# ID_logic.net
KiCad netlist of a schematic drawn in Altium Designer
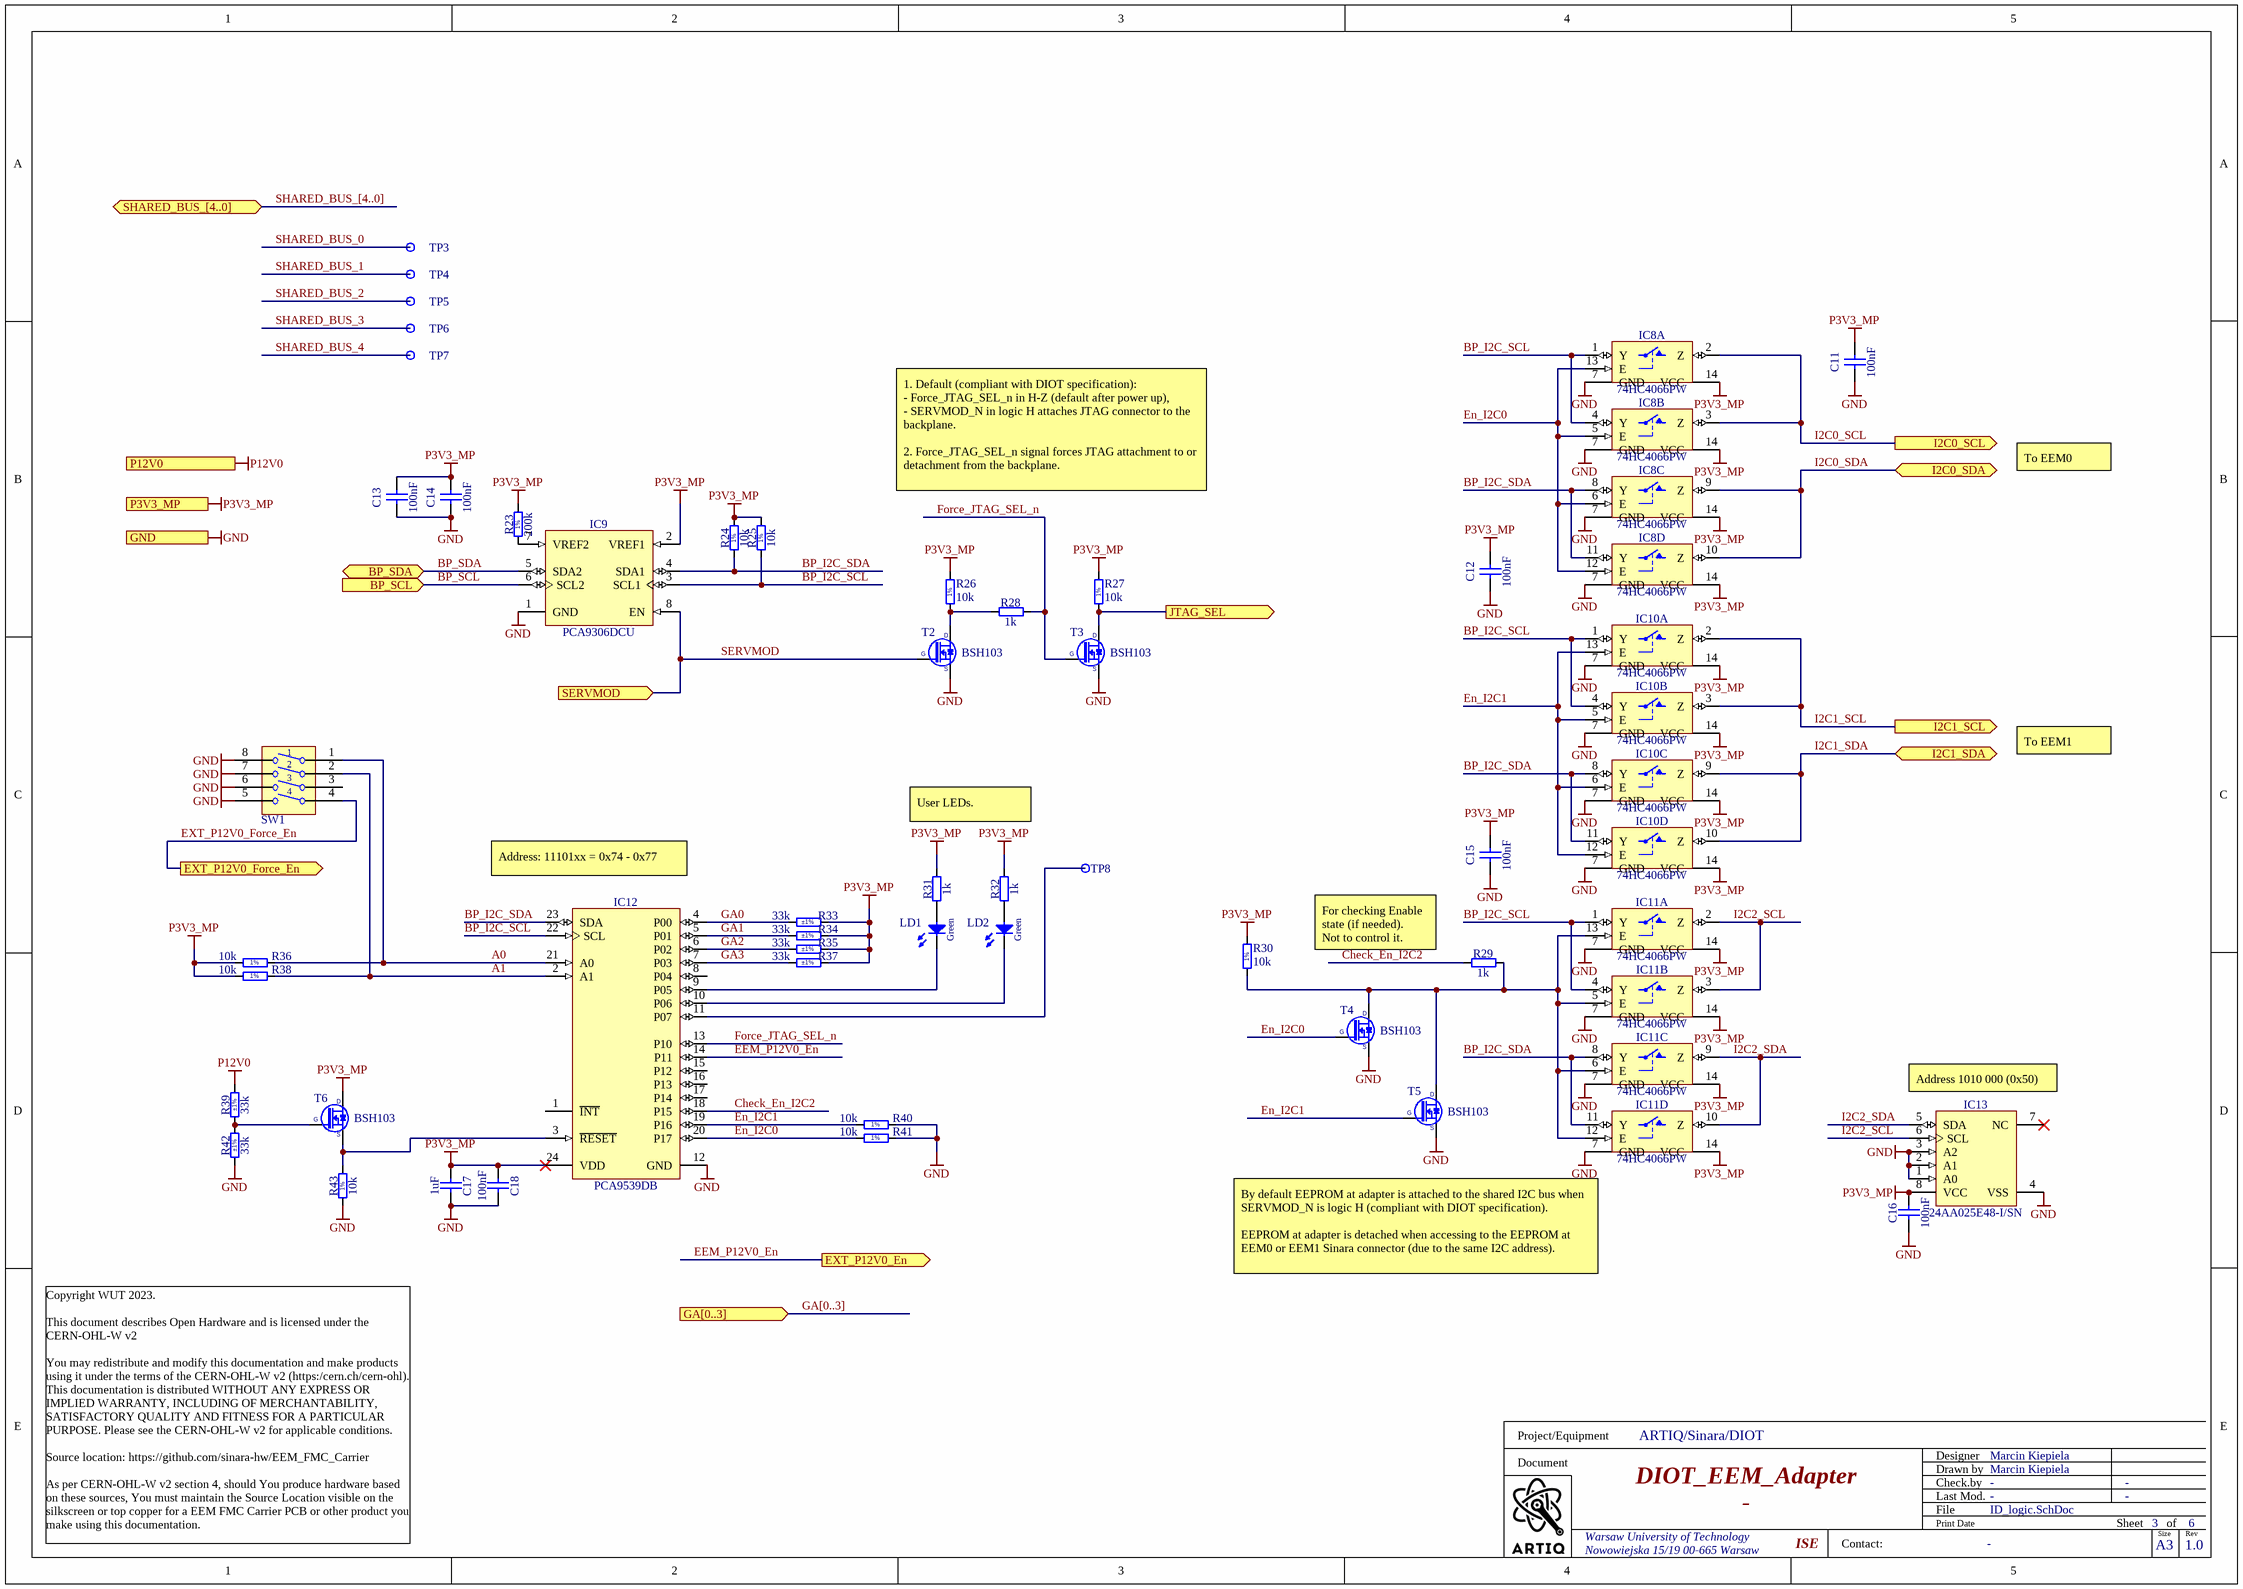
[diagram p0: ID_logic.SchDoc]

(export (version "E")
  (design (tool "Eeschema 10.0.6"))
  (components
    (comp (ref "C11")
      (value "100nF")
      (footprint "CAPC1005X55N")
      (description "Non-polarised capacitor")
      (fields
        (field (name "PART NUMBER") "CC0402_100NF_16V_10%_X7R")
        (field (name "VOLTAGE") "16V")
        (field (name "AUTHOR") "CERN DEM JLC")
      )
      (libsource (lib "Capacitors") (part "Capacitor - non polarized"))
    )
    (comp (ref "C12")
      (value "100nF")
      (footprint "CAPC1005X55N")
      (description "Non-polarised capacitor")
      (fields
        (field (name "PART NUMBER") "CC0402_100NF_16V_10%_X7R")
        (field (name "VOLTAGE") "16V")
        (field (name "AUTHOR") "CERN DEM JLC")
      )
      (libsource (lib "Capacitors") (part "Capacitor - non polarized"))
    )
    (comp (ref "C13")
      (value "100nF")
      (footprint "CAPC1005X55N")
      (description "Non-polarised capacitor")
      (fields
        (field (name "PART NUMBER") "CC0402_100NF_16V_10%_X7R")
        (field (name "VOLTAGE") "16V")
        (field (name "AUTHOR") "CERN DEM JLC")
      )
      (libsource (lib "Capacitors") (part "Capacitor - non polarized"))
    )
    (comp (ref "C14")
      (value "100nF")
      (footprint "CAPC1005X55N")
      (description "Non-polarised capacitor")
      (fields
        (field (name "PART NUMBER") "CC0402_100NF_16V_10%_X7R")
        (field (name "VOLTAGE") "16V")
        (field (name "AUTHOR") "CERN DEM JLC")
      )
      (libsource (lib "Capacitors") (part "Capacitor - non polarized"))
    )
    (comp (ref "C15")
      (value "100nF")
      (footprint "CAPC1005X55N")
      (description "Non-polarised capacitor")
      (fields
        (field (name "PART NUMBER") "CC0402_100NF_16V_10%_X7R")
        (field (name "VOLTAGE") "16V")
        (field (name "AUTHOR") "CERN DEM JLC")
      )
      (libsource (lib "Capacitors") (part "Capacitor - non polarized"))
    )
    (comp (ref "C16")
      (value "100nF")
      (footprint "CAPC1005X55N")
      (description "Non-polarised capacitor")
      (fields
        (field (name "PART NUMBER") "CC0402_100NF_16V_10%_X7R")
        (field (name "VOLTAGE") "16V")
        (field (name "AUTHOR") "CERN DEM JLC")
      )
      (libsource (lib "Capacitors") (part "Capacitor - non polarized"))
    )
    (comp (ref "C17")
      (value "1uF")
      (footprint "CAPC1608X87N")
      (description "Non-polarised capacitor")
      (fields
        (field (name "PART NUMBER") "CC0603_1UF_25V_10%_X7R")
        (field (name "VOLTAGE") "25V")
        (field (name "AUTHOR") "CERN DEM JLC")
      )
      (libsource (lib "Capacitors") (part "Capacitor - non polarized"))
    )
    (comp (ref "C18")
      (value "100nF")
      (footprint "CAPC1005X55N")
      (description "Non-polarised capacitor")
      (fields
        (field (name "PART NUMBER") "CC0402_100NF_16V_10%_X7R")
        (field (name "VOLTAGE") "16V")
        (field (name "AUTHOR") "CERN DEM JLC")
      )
      (libsource (lib "Capacitors") (part "Capacitor - non polarized"))
    )
    (comp (ref "IC8")
      (value "74HC4066PW")
      (footprint "SOP65P640X110-14N")
      (fields (field (name "MANUFACTURER") "NXP SEMICONDUCTORS") (field (name "AUTHOR") "CERN DEM JLC"))
      (libsource (lib "ICs And Semiconductors") (part "4066"))
    )
    (comp (ref "IC9")
      (value "PCA9306DCU")
      (footprint "SOP50P310X90-8N")
      (description "Dual Bidirectional I2C Bus And SMBus Voltage-Level Translator")
      (fields
        (field (name "PART NUMBER") "PCA9306DCUR")
        (field (name "MANUFACTURER") "TEXAS INSTRUMENTS")
        (field (name "AUTHOR") "CERN DEM JLC")
      )
      (libsource (lib "ICs And Semiconductors") (part "PCA9306D"))
    )
    (comp (ref "IC10")
      (value "74HC4066PW")
      (footprint "SOP65P640X110-14N")
      (fields (field (name "MANUFACTURER") "NXP SEMICONDUCTORS") (field (name "AUTHOR") "CERN DEM JLC"))
      (libsource (lib "ICs And Semiconductors") (part "4066"))
    )
    (comp (ref "IC11")
      (value "74HC4066PW")
      (footprint "SOP65P640X110-14N")
      (fields (field (name "MANUFACTURER") "NXP SEMICONDUCTORS") (field (name "AUTHOR") "CERN DEM JLC"))
      (libsource (lib "ICs And Semiconductors") (part "4066"))
    )
    (comp (ref "IC12")
      (value "PCA9539DB")
      (footprint "SOP65P780X200-24N")
      (fields (field (name "MANUFACTURER") "TEXAS INSTRUMENTS") (field (name "AUTHOR") "CERN DEM HF"))
      (libsource (lib "ICs And Semiconductors") (part "PCA9539DB"))
    )
    (comp (ref "IC13")
      (value "24AA025E48-I/SN")
      (footprint "SOIC127P600X175-8N")
      (description "1.7V-5.5V, 2K I2C™ Serial EEPROMs with EUI-48™ Node Identity")
      (fields (field (name "MANUFACTURER") "MICROCHIP TECHNOLOGY") (field (name "AUTHOR") "CERN DEM MR"))
      (libsource (lib "ICs And Semiconductors") (part "24AA025E48-I/SN"))
    )
    (comp (ref "LD1")
      (value "Green")
      (footprint "LED_KINGBRIGHT_KPH-1608CGCK")
      (description "LED Green 1C 2A")
      (fields
        (field (name "MANUFACTURER PART NUMBER") "KPH-1608CGCK")
        (field (name "PART NUMBER") "LED_KINGBRIGHT_KPH-1608CGCK")
        (field (name "AUTHOR") "CERN DEM JLC")
      )
      (libsource (lib "ICs And Semiconductors") (part "LED Green 1C 2A"))
    )
    (comp (ref "LD2")
      (value "Green")
      (footprint "LED_KINGBRIGHT_KPH-1608CGCK")
      (description "LED Green 1C 2A")
      (fields
        (field (name "MANUFACTURER PART NUMBER") "KPH-1608CGCK")
        (field (name "PART NUMBER") "LED_KINGBRIGHT_KPH-1608CGCK")
        (field (name "AUTHOR") "CERN DEM JLC")
      )
      (libsource (lib "ICs And Semiconductors") (part "LED Green 1C 2A"))
    )
    (comp (ref "R23")
      (value "200k")
      (footprint "RESC1005X40N")
      (description "Resistor - 1%")
      (fields
        (field (name "PART NUMBER") "R0402_200K_1%_0.0625W_100PPM")
        (field (name "POWER") "0.0625W")
        (field (name "AUTHOR") "CERN DEM JLC")
      )
      (libsource (lib "Resistors") (part "Resistor - 1%"))
    )
    (comp (ref "R24")
      (value "10k")
      (footprint "RESC1005X40N")
      (description "Resistor - 1%")
      (fields
        (field (name "PART NUMBER") "R0402_10K_1%_0.0625W_100PPM")
        (field (name "POWER") "0.0625W")
        (field (name "AUTHOR") "CERN DEM JLC")
      )
      (libsource (lib "Resistors") (part "Resistor - 1%"))
    )
    (comp (ref "R25")
      (value "10k")
      (footprint "RESC1005X40N")
      (description "Resistor - 1%")
      (fields
        (field (name "PART NUMBER") "R0402_10K_1%_0.0625W_100PPM")
        (field (name "POWER") "0.0625W")
        (field (name "AUTHOR") "CERN DEM JLC")
      )
      (libsource (lib "Resistors") (part "Resistor - 1%"))
    )
    (comp (ref "R26")
      (value "10k")
      (footprint "RESC1005X40N")
      (description "Resistor - 1%")
      (fields
        (field (name "PART NUMBER") "R0402_10K_1%_0.0625W_100PPM")
        (field (name "POWER") "0.0625W")
        (field (name "AUTHOR") "CERN DEM JLC")
      )
      (libsource (lib "Resistors") (part "Resistor - 1%"))
    )
    (comp (ref "R27")
      (value "10k")
      (footprint "RESC1005X40N")
      (description "Resistor - 1%")
      (fields
        (field (name "PART NUMBER") "R0402_10K_1%_0.0625W_100PPM")
        (field (name "POWER") "0.0625W")
        (field (name "AUTHOR") "CERN DEM JLC")
      )
      (libsource (lib "Resistors") (part "Resistor - 1%"))
    )
    (comp (ref "R28")
      (value "1k")
      (footprint "RESC1005X40N")
      (description "Resistor - 1%")
      (fields
        (field (name "PART NUMBER") "R0402_1K_1%_0.0625W_100PPM")
        (field (name "POWER") "0.0625W")
        (field (name "AUTHOR") "CERN DEM JLC")
      )
      (libsource (lib "Resistors") (part "Resistor - 1%"))
    )
    (comp (ref "R29")
      (value "1k")
      (footprint "RESC1005X40N")
      (description "Resistor - 1%")
      (fields
        (field (name "PART NUMBER") "R0402_1K_1%_0.0625W_100PPM")
        (field (name "POWER") "0.0625W")
        (field (name "AUTHOR") "CERN DEM JLC")
      )
      (libsource (lib "Resistors") (part "Resistor - 1%"))
    )
    (comp (ref "R30")
      (value "10k")
      (footprint "RESC1005X40N")
      (description "Resistor - 1%")
      (fields
        (field (name "PART NUMBER") "R0402_10K_1%_0.0625W_100PPM")
        (field (name "POWER") "0.0625W")
        (field (name "AUTHOR") "CERN DEM JLC")
      )
      (libsource (lib "Resistors") (part "Resistor - 1%"))
    )
    (comp (ref "R31")
      (value "1k")
      (footprint "RESC1005X40N")
      (description "Resistor - 1%")
      (fields
        (field (name "PART NUMBER") "R0402_1K_1%_0.0625W_100PPM")
        (field (name "POWER") "0.0625W")
        (field (name "AUTHOR") "CERN DEM JLC")
      )
      (libsource (lib "Resistors") (part "Resistor - 1%"))
    )
    (comp (ref "R32")
      (value "1k")
      (footprint "RESC1005X40N")
      (description "Resistor - 1%")
      (fields
        (field (name "PART NUMBER") "R0402_1K_1%_0.0625W_100PPM")
        (field (name "POWER") "0.0625W")
        (field (name "AUTHOR") "CERN DEM JLC")
      )
      (libsource (lib "Resistors") (part "Resistor - 1%"))
    )
    (comp (ref "R33")
      (value "33k")
      (footprint "RESC1005X40N")
      (description "Resistor - 1%")
      (fields
        (field (name "TOLERANCE") "±1%")
        (field (name "PART NUMBER") "R0402_33K_1%_0.0625W_100PPM")
        (field (name "POWER") "0.0625W")
        (field (name "AUTHOR") "CERN DEM JLC")
      )
      (libsource (lib "Resistors") (part "Resistor - 1%"))
    )
    (comp (ref "R34")
      (value "33k")
      (footprint "RESC1005X40N")
      (description "Resistor - 1%")
      (fields
        (field (name "TOLERANCE") "±1%")
        (field (name "PART NUMBER") "R0402_33K_1%_0.0625W_100PPM")
        (field (name "POWER") "0.0625W")
        (field (name "AUTHOR") "CERN DEM JLC")
      )
      (libsource (lib "Resistors") (part "Resistor - 1%"))
    )
    (comp (ref "R35")
      (value "33k")
      (footprint "RESC1005X40N")
      (description "Resistor - 1%")
      (fields
        (field (name "TOLERANCE") "±1%")
        (field (name "PART NUMBER") "R0402_33K_1%_0.0625W_100PPM")
        (field (name "POWER") "0.0625W")
        (field (name "AUTHOR") "CERN DEM JLC")
      )
      (libsource (lib "Resistors") (part "Resistor - 1%"))
    )
    (comp (ref "R36")
      (value "10k")
      (footprint "RESC1005X40N")
      (description "Resistor - 1%")
      (fields
        (field (name "PART NUMBER") "R0402_10K_1%_0.0625W_100PPM")
        (field (name "POWER") "0.0625W")
        (field (name "AUTHOR") "CERN DEM JLC")
      )
      (libsource (lib "Resistors") (part "Resistor - 1%"))
    )
    (comp (ref "R37")
      (value "33k")
      (footprint "RESC1005X40N")
      (description "Resistor - 1%")
      (fields
        (field (name "TOLERANCE") "±1%")
        (field (name "PART NUMBER") "R0402_33K_1%_0.0625W_100PPM")
        (field (name "POWER") "0.0625W")
        (field (name "AUTHOR") "CERN DEM JLC")
      )
      (libsource (lib "Resistors") (part "Resistor - 1%"))
    )
    (comp (ref "R38")
      (value "10k")
      (footprint "RESC1005X40N")
      (description "Resistor - 1%")
      (fields
        (field (name "PART NUMBER") "R0402_10K_1%_0.0625W_100PPM")
        (field (name "POWER") "0.0625W")
        (field (name "AUTHOR") "CERN DEM JLC")
      )
      (libsource (lib "Resistors") (part "Resistor - 1%"))
    )
    (comp (ref "R39")
      (value "33k")
      (footprint "RESC1005X40N")
      (description "Resistor - 1%")
      (fields
        (field (name "TOLERANCE") "±1%")
        (field (name "PART NUMBER") "R0402_33K_1%_0.0625W_100PPM")
        (field (name "POWER") "0.0625W")
        (field (name "AUTHOR") "CERN DEM JLC")
      )
      (libsource (lib "Resistors") (part "Resistor - 1%"))
    )
    (comp (ref "R40")
      (value "10k")
      (footprint "RESC1005X40N")
      (description "Resistor - 1%")
      (fields
        (field (name "PART NUMBER") "R0402_10K_1%_0.0625W_100PPM")
        (field (name "POWER") "0.0625W")
        (field (name "AUTHOR") "CERN DEM JLC")
      )
      (libsource (lib "Resistors") (part "Resistor - 1%"))
    )
    (comp (ref "R41")
      (value "10k")
      (footprint "RESC1005X40N")
      (description "Resistor - 1%")
      (fields
        (field (name "PART NUMBER") "R0402_10K_1%_0.0625W_100PPM")
        (field (name "POWER") "0.0625W")
        (field (name "AUTHOR") "CERN DEM JLC")
      )
      (libsource (lib "Resistors") (part "Resistor - 1%"))
    )
    (comp (ref "R42")
      (value "33k")
      (footprint "RESC1005X40N")
      (description "Resistor - 1%")
      (fields
        (field (name "TOLERANCE") "±1%")
        (field (name "PART NUMBER") "R0402_33K_1%_0.0625W_100PPM")
        (field (name "POWER") "0.0625W")
        (field (name "AUTHOR") "CERN DEM JLC")
      )
      (libsource (lib "Resistors") (part "Resistor - 1%"))
    )
    (comp (ref "R43")
      (value "10k")
      (footprint "RESC1005X40N")
      (description "Resistor - 1%")
      (fields
        (field (name "PART NUMBER") "R0402_10K_1%_0.0625W_100PPM")
        (field (name "POWER") "0.0625W")
        (field (name "AUTHOR") "CERN DEM JLC")
      )
      (libsource (lib "Resistors") (part "Resistor - 1%"))
    )
    (comp (ref "SW1")
      (value "Switch")
      (footprint "SW_OMRON_A6S-4102-H")
      (description "4 Ways SPST DIP Switch")
      (fields
        (field (name "PART NUMBER") "SW_OMRON_A6S-4102-H")
        (field (name "MANUFACTURER") "OMRON")
        (field (name "AUTHOR") "CERN DEM JMW")
      )
      (libsource (lib "Eletro-mechanical") (part "SW 4x SPST DIP Switch"))
    )
    (comp (ref "T2")
      (value "BSH103")
      (footprint "SOT95P230X110-3N")
      (description "N-CHANNEL MOSFET WITH DIODE")
      (fields (field (name "MANUFACTURER") "NEXPERIA") (field (name "AUTHOR") "CERN DEM JLC"))
      (libsource (lib "ICs And Semiconductors") (part "N-MOSFET-D 1G 2S 3D"))
    )
    (comp (ref "T3")
      (value "BSH103")
      (footprint "SOT95P230X110-3N")
      (description "N-CHANNEL MOSFET WITH DIODE")
      (fields (field (name "MANUFACTURER") "NEXPERIA") (field (name "AUTHOR") "CERN DEM JLC"))
      (libsource (lib "ICs And Semiconductors") (part "N-MOSFET-D 1G 2S 3D"))
    )
    (comp (ref "T4")
      (value "BSH103")
      (footprint "SOT95P230X110-3N")
      (description "N-CHANNEL MOSFET WITH DIODE")
      (fields (field (name "MANUFACTURER") "NEXPERIA") (field (name "AUTHOR") "CERN DEM JLC"))
      (libsource (lib "ICs And Semiconductors") (part "N-MOSFET-D 1G 2S 3D"))
    )
    (comp (ref "T5")
      (value "BSH103")
      (footprint "SOT95P230X110-3N")
      (description "N-CHANNEL MOSFET WITH DIODE")
      (fields (field (name "MANUFACTURER") "NEXPERIA") (field (name "AUTHOR") "CERN DEM JLC"))
      (libsource (lib "ICs And Semiconductors") (part "N-MOSFET-D 1G 2S 3D"))
    )
    (comp (ref "T6")
      (value "BSH103")
      (footprint "SOT95P230X110-3N")
      (description "N-CHANNEL MOSFET WITH DIODE")
      (fields (field (name "MANUFACTURER") "NEXPERIA") (field (name "AUTHOR") "CERN DEM JLC"))
      (libsource (lib "ICs And Semiconductors") (part "N-MOSFET-D 1G 2S 3D"))
    )
    (comp (ref "TP3")
      (value "Test Point")
      (footprint "TPS127")
      (fields (field (name "PART NUMBER") "SMD_PAD_1.27X1.27MM") (field (name "AUTHOR") "CERN DEM JLC"))
      (libsource (lib "Eletro-mechanical") (part "Test Point"))
    )
    (comp (ref "TP4")
      (value "Test Point")
      (footprint "TPS127")
      (fields (field (name "PART NUMBER") "SMD_PAD_1.27X1.27MM") (field (name "AUTHOR") "CERN DEM JLC"))
      (libsource (lib "Eletro-mechanical") (part "Test Point"))
    )
    (comp (ref "TP5")
      (value "Test Point")
      (footprint "TPS127")
      (fields (field (name "PART NUMBER") "SMD_PAD_1.27X1.27MM") (field (name "AUTHOR") "CERN DEM JLC"))
      (libsource (lib "Eletro-mechanical") (part "Test Point"))
    )
    (comp (ref "TP6")
      (value "Test Point")
      (footprint "TPS127")
      (fields (field (name "PART NUMBER") "SMD_PAD_1.27X1.27MM") (field (name "AUTHOR") "CERN DEM JLC"))
      (libsource (lib "Eletro-mechanical") (part "Test Point"))
    )
    (comp (ref "TP7")
      (value "Test Point")
      (footprint "TPS127")
      (fields (field (name "PART NUMBER") "SMD_PAD_1.27X1.27MM") (field (name "AUTHOR") "CERN DEM JLC"))
      (libsource (lib "Eletro-mechanical") (part "Test Point"))
    )
    (comp (ref "TP8")
      (value "Test Point")
      (footprint "TPS127")
      (fields (field (name "PART NUMBER") "SMD_PAD_1.27X1.27MM") (field (name "AUTHOR") "CERN DEM JLC"))
      (libsource (lib "Eletro-mechanical") (part "Test Point"))
    )
  )
  (nets
    (net (code "1") (name "/A0") (class "Default")
      (node (ref "IC12") (pin "21") (pinfunction "A0_21") (pintype "input"))
      (node (ref "R36") (pin "2") (pinfunction "2_2") (pintype "passive"))
      (node (ref "SW1") (pin "1") (pinfunction "1_1") (pintype "passive"))
    )
    (net (code "2") (name "/A1") (class "Default")
      (node (ref "IC12") (pin "2") (pinfunction "A1_2") (pintype "input"))
      (node (ref "R38") (pin "2") (pinfunction "2_2") (pintype "passive"))
      (node (ref "SW1") (pin "2") (pinfunction "2_2") (pintype "passive"))
    )
    (net (code "3") (name "/BP_I2C_SCL") (class "Default")
      (node (ref "IC10") (pin "1") (pinfunction "Y_1") (pintype "bidirectional"))
      (node (ref "IC10") (pin "4") (pinfunction "Y_4") (pintype "bidirectional"))
      (node (ref "IC11") (pin "1") (pinfunction "Y_1") (pintype "bidirectional"))
      (node (ref "IC11") (pin "4") (pinfunction "Y_4") (pintype "bidirectional"))
      (node (ref "IC12") (pin "22") (pinfunction "SCL_22") (pintype "input"))
      (node (ref "IC8") (pin "1") (pinfunction "Y_1") (pintype "bidirectional"))
      (node (ref "IC8") (pin "4") (pinfunction "Y_4") (pintype "bidirectional"))
      (node (ref "IC9") (pin "3") (pinfunction "SCL1_3") (pintype "bidirectional"))
      (node (ref "R25") (pin "1") (pinfunction "1_1") (pintype "passive"))
    )
    (net (code "4") (name "/BP_I2C_SDA") (class "Default")
      (node (ref "IC10") (pin "11") (pinfunction "Y_11") (pintype "bidirectional"))
      (node (ref "IC10") (pin "8") (pinfunction "Y_8") (pintype "bidirectional"))
      (node (ref "IC11") (pin "11") (pinfunction "Y_11") (pintype "bidirectional"))
      (node (ref "IC11") (pin "8") (pinfunction "Y_8") (pintype "bidirectional"))
      (node (ref "IC12") (pin "23") (pinfunction "SDA_23") (pintype "bidirectional"))
      (node (ref "IC8") (pin "11") (pinfunction "Y_11") (pintype "bidirectional"))
      (node (ref "IC8") (pin "8") (pinfunction "Y_8") (pintype "bidirectional"))
      (node (ref "IC9") (pin "4") (pinfunction "SDA1_4") (pintype "bidirectional"))
      (node (ref "R24") (pin "1") (pinfunction "1_1") (pintype "passive"))
    )
    (net (code "5") (name "/BP_SCL") (class "Default")
      (node (ref "IC9") (pin "6") (pinfunction "SCL2_6") (pintype "bidirectional"))
    )
    (net (code "6") (name "/BP_SDA") (class "Default")
      (node (ref "IC9") (pin "5") (pinfunction "SDA2_5") (pintype "bidirectional"))
    )
    (net (code "7") (name "/Check_En_I2C2") (class "Default")
      (node (ref "IC12") (pin "18") (pinfunction "P15_18") (pintype "bidirectional"))
      (node (ref "R29") (pin "1") (pinfunction "1_1") (pintype "passive"))
    )
    (net (code "8") (name "/EEM_P12V0_En") (class "Default")
      (node (ref "IC12") (pin "14") (pinfunction "P11_14") (pintype "bidirectional"))
    )
    (net (code "9") (name "/EXT_P12V0_Force_En") (class "Default")
      (node (ref "SW1") (pin "4") (pinfunction "4_4") (pintype "passive"))
    )
    (net (code "10") (name "/En_I2C0") (class "Default")
      (node (ref "IC12") (pin "20") (pinfunction "P17_20") (pintype "bidirectional"))
      (node (ref "IC8") (pin "12") (pinfunction "E_12") (pintype "input"))
      (node (ref "IC8") (pin "13") (pinfunction "E_13") (pintype "input"))
      (node (ref "IC8") (pin "5") (pinfunction "E_5") (pintype "input"))
      (node (ref "IC8") (pin "6") (pinfunction "E_6") (pintype "input"))
      (node (ref "R41") (pin "1") (pinfunction "1_1") (pintype "passive"))
      (node (ref "T4") (pin "1") (pinfunction "G_1") (pintype "passive"))
    )
    (net (code "11") (name "/En_I2C1") (class "Default")
      (node (ref "IC10") (pin "12") (pinfunction "E_12") (pintype "input"))
      (node (ref "IC10") (pin "13") (pinfunction "E_13") (pintype "input"))
      (node (ref "IC10") (pin "5") (pinfunction "E_5") (pintype "input"))
      (node (ref "IC10") (pin "6") (pinfunction "E_6") (pintype "input"))
      (node (ref "IC12") (pin "19") (pinfunction "P16_19") (pintype "bidirectional"))
      (node (ref "R40") (pin "1") (pinfunction "1_1") (pintype "passive"))
      (node (ref "T5") (pin "1") (pinfunction "G_1") (pintype "passive"))
    )
    (net (code "12") (name "/Force_JTAG_SEL_n") (class "Default")
      (node (ref "IC12") (pin "13") (pinfunction "P10_13") (pintype "bidirectional"))
      (node (ref "R28") (pin "2") (pinfunction "2_2") (pintype "passive"))
      (node (ref "T3") (pin "1") (pinfunction "G_1") (pintype "passive"))
    )
    (net (code "13") (name "/GA0") (class "Default")
      (node (ref "IC12") (pin "4") (pinfunction "P00_4") (pintype "bidirectional"))
      (node (ref "R33") (pin "1") (pinfunction "1_1") (pintype "passive"))
    )
    (net (code "14") (name "/GA1") (class "Default")
      (node (ref "IC12") (pin "5") (pinfunction "P01_5") (pintype "bidirectional"))
      (node (ref "R34") (pin "1") (pinfunction "1_1") (pintype "passive"))
    )
    (net (code "15") (name "/GA2") (class "Default")
      (node (ref "IC12") (pin "6") (pinfunction "P02_6") (pintype "bidirectional"))
      (node (ref "R35") (pin "1") (pinfunction "1_1") (pintype "passive"))
    )
    (net (code "16") (name "/GA3") (class "Default")
      (node (ref "IC12") (pin "7") (pinfunction "P03_7") (pintype "bidirectional"))
      (node (ref "R37") (pin "1") (pinfunction "1_1") (pintype "passive"))
    )
    (net (code "18") (name "/I2C0_SCL") (class "Default")
      (node (ref "IC8") (pin "2") (pinfunction "Z_2") (pintype "bidirectional"))
      (node (ref "IC8") (pin "3") (pinfunction "Z_3") (pintype "bidirectional"))
    )
    (net (code "19") (name "/I2C0_SDA") (class "Default")
      (node (ref "IC8") (pin "10") (pinfunction "Z_10") (pintype "bidirectional"))
      (node (ref "IC8") (pin "9") (pinfunction "Z_9") (pintype "bidirectional"))
    )
    (net (code "20") (name "/I2C1_SCL") (class "Default")
      (node (ref "IC10") (pin "2") (pinfunction "Z_2") (pintype "bidirectional"))
      (node (ref "IC10") (pin "3") (pinfunction "Z_3") (pintype "bidirectional"))
    )
    (net (code "21") (name "/I2C1_SDA") (class "Default")
      (node (ref "IC10") (pin "10") (pinfunction "Z_10") (pintype "bidirectional"))
      (node (ref "IC10") (pin "9") (pinfunction "Z_9") (pintype "bidirectional"))
    )
    (net (code "22") (name "/I2C2_SCL") (class "Default")
      (node (ref "IC11") (pin "2") (pinfunction "Z_2") (pintype "bidirectional"))
      (node (ref "IC11") (pin "3") (pinfunction "Z_3") (pintype "bidirectional"))
      (node (ref "IC13") (pin "6") (pinfunction "SCL_6") (pintype "input"))
    )
    (net (code "23") (name "/I2C2_SDA") (class "Default")
      (node (ref "IC11") (pin "10") (pinfunction "Z_10") (pintype "bidirectional"))
      (node (ref "IC11") (pin "9") (pinfunction "Z_9") (pintype "bidirectional"))
      (node (ref "IC13") (pin "5") (pinfunction "SDA_5") (pintype "bidirectional"))
    )
    (net (code "24") (name "/JTAG_SEL") (class "Default")
      (node (ref "R27") (pin "1") (pinfunction "1_1") (pintype "passive"))
      (node (ref "T3") (pin "3") (pinfunction "D_3") (pintype "passive"))
    )
    (net (code "25") (name "/SERVMOD") (class "Default")
      (node (ref "IC9") (pin "8") (pinfunction "EN_8") (pintype "input"))
      (node (ref "T2") (pin "1") (pinfunction "G_1") (pintype "passive"))
    )
    (net (code "26") (name "/SHARED_BUS_0") (class "Default")
      (node (ref "TP3") (pin "1") (pinfunction "1_1") (pintype "bidirectional"))
    )
    (net (code "27") (name "/SHARED_BUS_1") (class "Default")
      (node (ref "TP4") (pin "1") (pinfunction "1_1") (pintype "bidirectional"))
    )
    (net (code "28") (name "/SHARED_BUS_2") (class "Default")
      (node (ref "TP5") (pin "1") (pinfunction "1_1") (pintype "bidirectional"))
    )
    (net (code "29") (name "/SHARED_BUS_3") (class "Default")
      (node (ref "TP6") (pin "1") (pinfunction "1_1") (pintype "bidirectional"))
    )
    (net (code "30") (name "/SHARED_BUS_4") (class "Default")
      (node (ref "TP7") (pin "1") (pinfunction "1_1") (pintype "bidirectional"))
    )
    (net (code "32") (name "GND") (class "Default")
      (node (ref "C11") (pin "1") (pinfunction "1_1") (pintype "passive"))
      (node (ref "C12") (pin "1") (pinfunction "1_1") (pintype "passive"))
      (node (ref "C13") (pin "1") (pinfunction "1_1") (pintype "passive"))
      (node (ref "C14") (pin "1") (pinfunction "1_1") (pintype "passive"))
      (node (ref "C15") (pin "1") (pinfunction "1_1") (pintype "passive"))
      (node (ref "C16") (pin "1") (pinfunction "1_1") (pintype "passive"))
      (node (ref "C17") (pin "1") (pinfunction "1_1") (pintype "passive"))
      (node (ref "C18") (pin "1") (pinfunction "1_1") (pintype "passive"))
      (node (ref "IC10") (pin "7") (pinfunction "GND_7") (pintype "power_in"))
      (node (ref "IC11") (pin "7") (pinfunction "GND_7") (pintype "power_in"))
      (node (ref "IC12") (pin "12") (pinfunction "GND_12") (pintype "power_in"))
      (node (ref "IC13") (pin "1") (pinfunction "A0_1") (pintype "input"))
      (node (ref "IC13") (pin "2") (pinfunction "A1_2") (pintype "input"))
      (node (ref "IC13") (pin "3") (pinfunction "A2_3") (pintype "input"))
      (node (ref "IC13") (pin "4") (pinfunction "VSS_4") (pintype "power_in"))
      (node (ref "IC8") (pin "7") (pinfunction "GND_7") (pintype "power_in"))
      (node (ref "IC9") (pin "1") (pinfunction "GND_1") (pintype "power_in"))
      (node (ref "R40") (pin "2") (pinfunction "2_2") (pintype "passive"))
      (node (ref "R41") (pin "2") (pinfunction "2_2") (pintype "passive"))
      (node (ref "R42") (pin "1") (pinfunction "1_1") (pintype "passive"))
      (node (ref "R43") (pin "1") (pinfunction "1_1") (pintype "passive"))
      (node (ref "SW1") (pin "5") (pinfunction "5_5") (pintype "passive"))
      (node (ref "SW1") (pin "6") (pinfunction "6_6") (pintype "passive"))
      (node (ref "SW1") (pin "7") (pinfunction "7_7") (pintype "passive"))
      (node (ref "SW1") (pin "8") (pinfunction "8_8") (pintype "passive"))
      (node (ref "T2") (pin "2") (pinfunction "S_2") (pintype "passive"))
      (node (ref "T3") (pin "2") (pinfunction "S_2") (pintype "passive"))
      (node (ref "T4") (pin "2") (pinfunction "S_2") (pintype "passive"))
      (node (ref "T5") (pin "2") (pinfunction "S_2") (pintype "passive"))
    )
    (net (code "33") (name "Net-(IC9-VREF2)") (class "Default")
      (node (ref "IC9") (pin "7") (pinfunction "VREF2_7") (pintype "input"))
      (node (ref "R23") (pin "1") (pinfunction "1_1") (pintype "passive"))
    )
    (net (code "34") (name "Net-(IC11A-E)") (class "Default")
      (node (ref "IC11") (pin "12") (pinfunction "E_12") (pintype "input"))
      (node (ref "IC11") (pin "13") (pinfunction "E_13") (pintype "input"))
      (node (ref "IC11") (pin "5") (pinfunction "E_5") (pintype "input"))
      (node (ref "IC11") (pin "6") (pinfunction "E_6") (pintype "input"))
      (node (ref "R29") (pin "2") (pinfunction "2_2") (pintype "passive"))
      (node (ref "R30") (pin "1") (pinfunction "1_1") (pintype "passive"))
      (node (ref "T4") (pin "3") (pinfunction "D_3") (pintype "passive"))
      (node (ref "T5") (pin "3") (pinfunction "D_3") (pintype "passive"))
    )
    (net (code "35") (name "Net-(IC12-P05)") (class "Default")
      (node (ref "IC12") (pin "9") (pinfunction "P05_9") (pintype "bidirectional"))
      (node (ref "LD1") (pin "1") (pinfunction "C_1") (pintype "passive"))
    )
    (net (code "36") (name "Net-(IC12-P06)") (class "Default")
      (node (ref "IC12") (pin "10") (pinfunction "P06_10") (pintype "bidirectional"))
      (node (ref "LD2") (pin "1") (pinfunction "C_1") (pintype "passive"))
    )
    (net (code "37") (name "Net-(IC12-P07)") (class "Default")
      (node (ref "IC12") (pin "11") (pinfunction "P07_11") (pintype "bidirectional"))
      (node (ref "TP8") (pin "1") (pinfunction "1_1") (pintype "bidirectional"))
    )
    (net (code "38") (name "Net-(IC12-~{RESET})") (class "Default")
      (node (ref "IC12") (pin "3") (pinfunction "~{RESET}_3") (pintype "input"))
      (node (ref "R43") (pin "2") (pinfunction "2_2") (pintype "passive"))
      (node (ref "T6") (pin "2") (pinfunction "S_2") (pintype "passive"))
    )
    (net (code "39") (name "Net-(LD1-A)") (class "Default")
      (node (ref "LD1") (pin "2") (pinfunction "A_2") (pintype "passive"))
      (node (ref "R31") (pin "1") (pinfunction "1_1") (pintype "passive"))
    )
    (net (code "40") (name "Net-(LD2-A)") (class "Default")
      (node (ref "LD2") (pin "2") (pinfunction "A_2") (pintype "passive"))
      (node (ref "R32") (pin "1") (pinfunction "1_1") (pintype "passive"))
    )
    (net (code "41") (name "Net-(T2-D)") (class "Default")
      (node (ref "R26") (pin "1") (pinfunction "1_1") (pintype "passive"))
      (node (ref "R28") (pin "1") (pinfunction "1_1") (pintype "passive"))
      (node (ref "T2") (pin "3") (pinfunction "D_3") (pintype "passive"))
    )
    (net (code "42") (name "Net-(T6-G)") (class "Default")
      (node (ref "R39") (pin "1") (pinfunction "1_1") (pintype "passive"))
      (node (ref "R42") (pin "2") (pinfunction "2_2") (pintype "passive"))
      (node (ref "T6") (pin "1") (pinfunction "G_1") (pintype "passive"))
    )
    (net (code "43") (name "P3V3_MP") (class "Default")
      (node (ref "C11") (pin "2") (pinfunction "2_2") (pintype "passive"))
      (node (ref "C12") (pin "2") (pinfunction "2_2") (pintype "passive"))
      (node (ref "C13") (pin "2") (pinfunction "2_2") (pintype "passive"))
      (node (ref "C14") (pin "2") (pinfunction "2_2") (pintype "passive"))
      (node (ref "C15") (pin "2") (pinfunction "2_2") (pintype "passive"))
      (node (ref "C16") (pin "2") (pinfunction "2_2") (pintype "passive"))
      (node (ref "C17") (pin "2") (pinfunction "2_2") (pintype "passive"))
      (node (ref "C18") (pin "2") (pinfunction "2_2") (pintype "passive"))
      (node (ref "IC10") (pin "14") (pinfunction "VCC_14") (pintype "power_in"))
      (node (ref "IC11") (pin "14") (pinfunction "VCC_14") (pintype "power_in"))
      (node (ref "IC12") (pin "24") (pinfunction "VDD_24") (pintype "power_in"))
      (node (ref "IC13") (pin "8") (pinfunction "VCC_8") (pintype "power_in"))
      (node (ref "IC8") (pin "14") (pinfunction "VCC_14") (pintype "power_in"))
      (node (ref "IC9") (pin "2") (pinfunction "VREF1_2") (pintype "input"))
      (node (ref "R23") (pin "2") (pinfunction "2_2") (pintype "passive"))
      (node (ref "R24") (pin "2") (pinfunction "2_2") (pintype "passive"))
      (node (ref "R25") (pin "2") (pinfunction "2_2") (pintype "passive"))
      (node (ref "R26") (pin "2") (pinfunction "2_2") (pintype "passive"))
      (node (ref "R27") (pin "2") (pinfunction "2_2") (pintype "passive"))
      (node (ref "R30") (pin "2") (pinfunction "2_2") (pintype "passive"))
      (node (ref "R31") (pin "2") (pinfunction "2_2") (pintype "passive"))
      (node (ref "R32") (pin "2") (pinfunction "2_2") (pintype "passive"))
      (node (ref "R33") (pin "2") (pinfunction "2_2") (pintype "passive"))
      (node (ref "R34") (pin "2") (pinfunction "2_2") (pintype "passive"))
      (node (ref "R35") (pin "2") (pinfunction "2_2") (pintype "passive"))
      (node (ref "R36") (pin "1") (pinfunction "1_1") (pintype "passive"))
      (node (ref "R37") (pin "2") (pinfunction "2_2") (pintype "passive"))
      (node (ref "R38") (pin "1") (pinfunction "1_1") (pintype "passive"))
      (node (ref "T6") (pin "3") (pinfunction "D_3") (pintype "passive"))
    )
    (net (code "44") (name "P12V0") (class "Default")
      (node (ref "R39") (pin "2") (pinfunction "2_2") (pintype "passive"))
    )
    (net (code "45") (name "unconnected-(IC12-P04-Pad8)") (class "Default")
      (node (ref "IC12") (pin "8") (pinfunction "P04_8") (pintype "bidirectional"))
    )
    (net (code "46") (name "unconnected-(IC12-P12-Pad15)") (class "Default")
      (node (ref "IC12") (pin "15") (pinfunction "P12_15") (pintype "bidirectional"))
    )
    (net (code "47") (name "unconnected-(IC12-P13-Pad16)") (class "Default")
      (node (ref "IC12") (pin "16") (pinfunction "P13_16") (pintype "bidirectional"))
    )
    (net (code "48") (name "unconnected-(IC12-P14-Pad17)") (class "Default")
      (node (ref "IC12") (pin "17") (pinfunction "P14_17") (pintype "bidirectional"))
    )
    (net (code "49") (name "unconnected-(IC12-~{INT}-Pad1)") (class "Default")
      (node (ref "IC12") (pin "1") (pinfunction "~{INT}_1") (pintype "open_collector"))
    )
    (net (code "50") (name "unconnected-(IC13-NC-Pad7)") (class "Default")
      (node (ref "IC13") (pin "7") (pinfunction "NC_7") (pintype "passive+no_connect"))
    )
    (net (code "51") (name "unconnected-(SW1-Pad3)") (class "Default")
      (node (ref "SW1") (pin "3") (pinfunction "3_3") (pintype "passive"))
    )
  )
)
